# Giao_Thong.net
KiCad netlist of a schematic drawn in Altium Designer
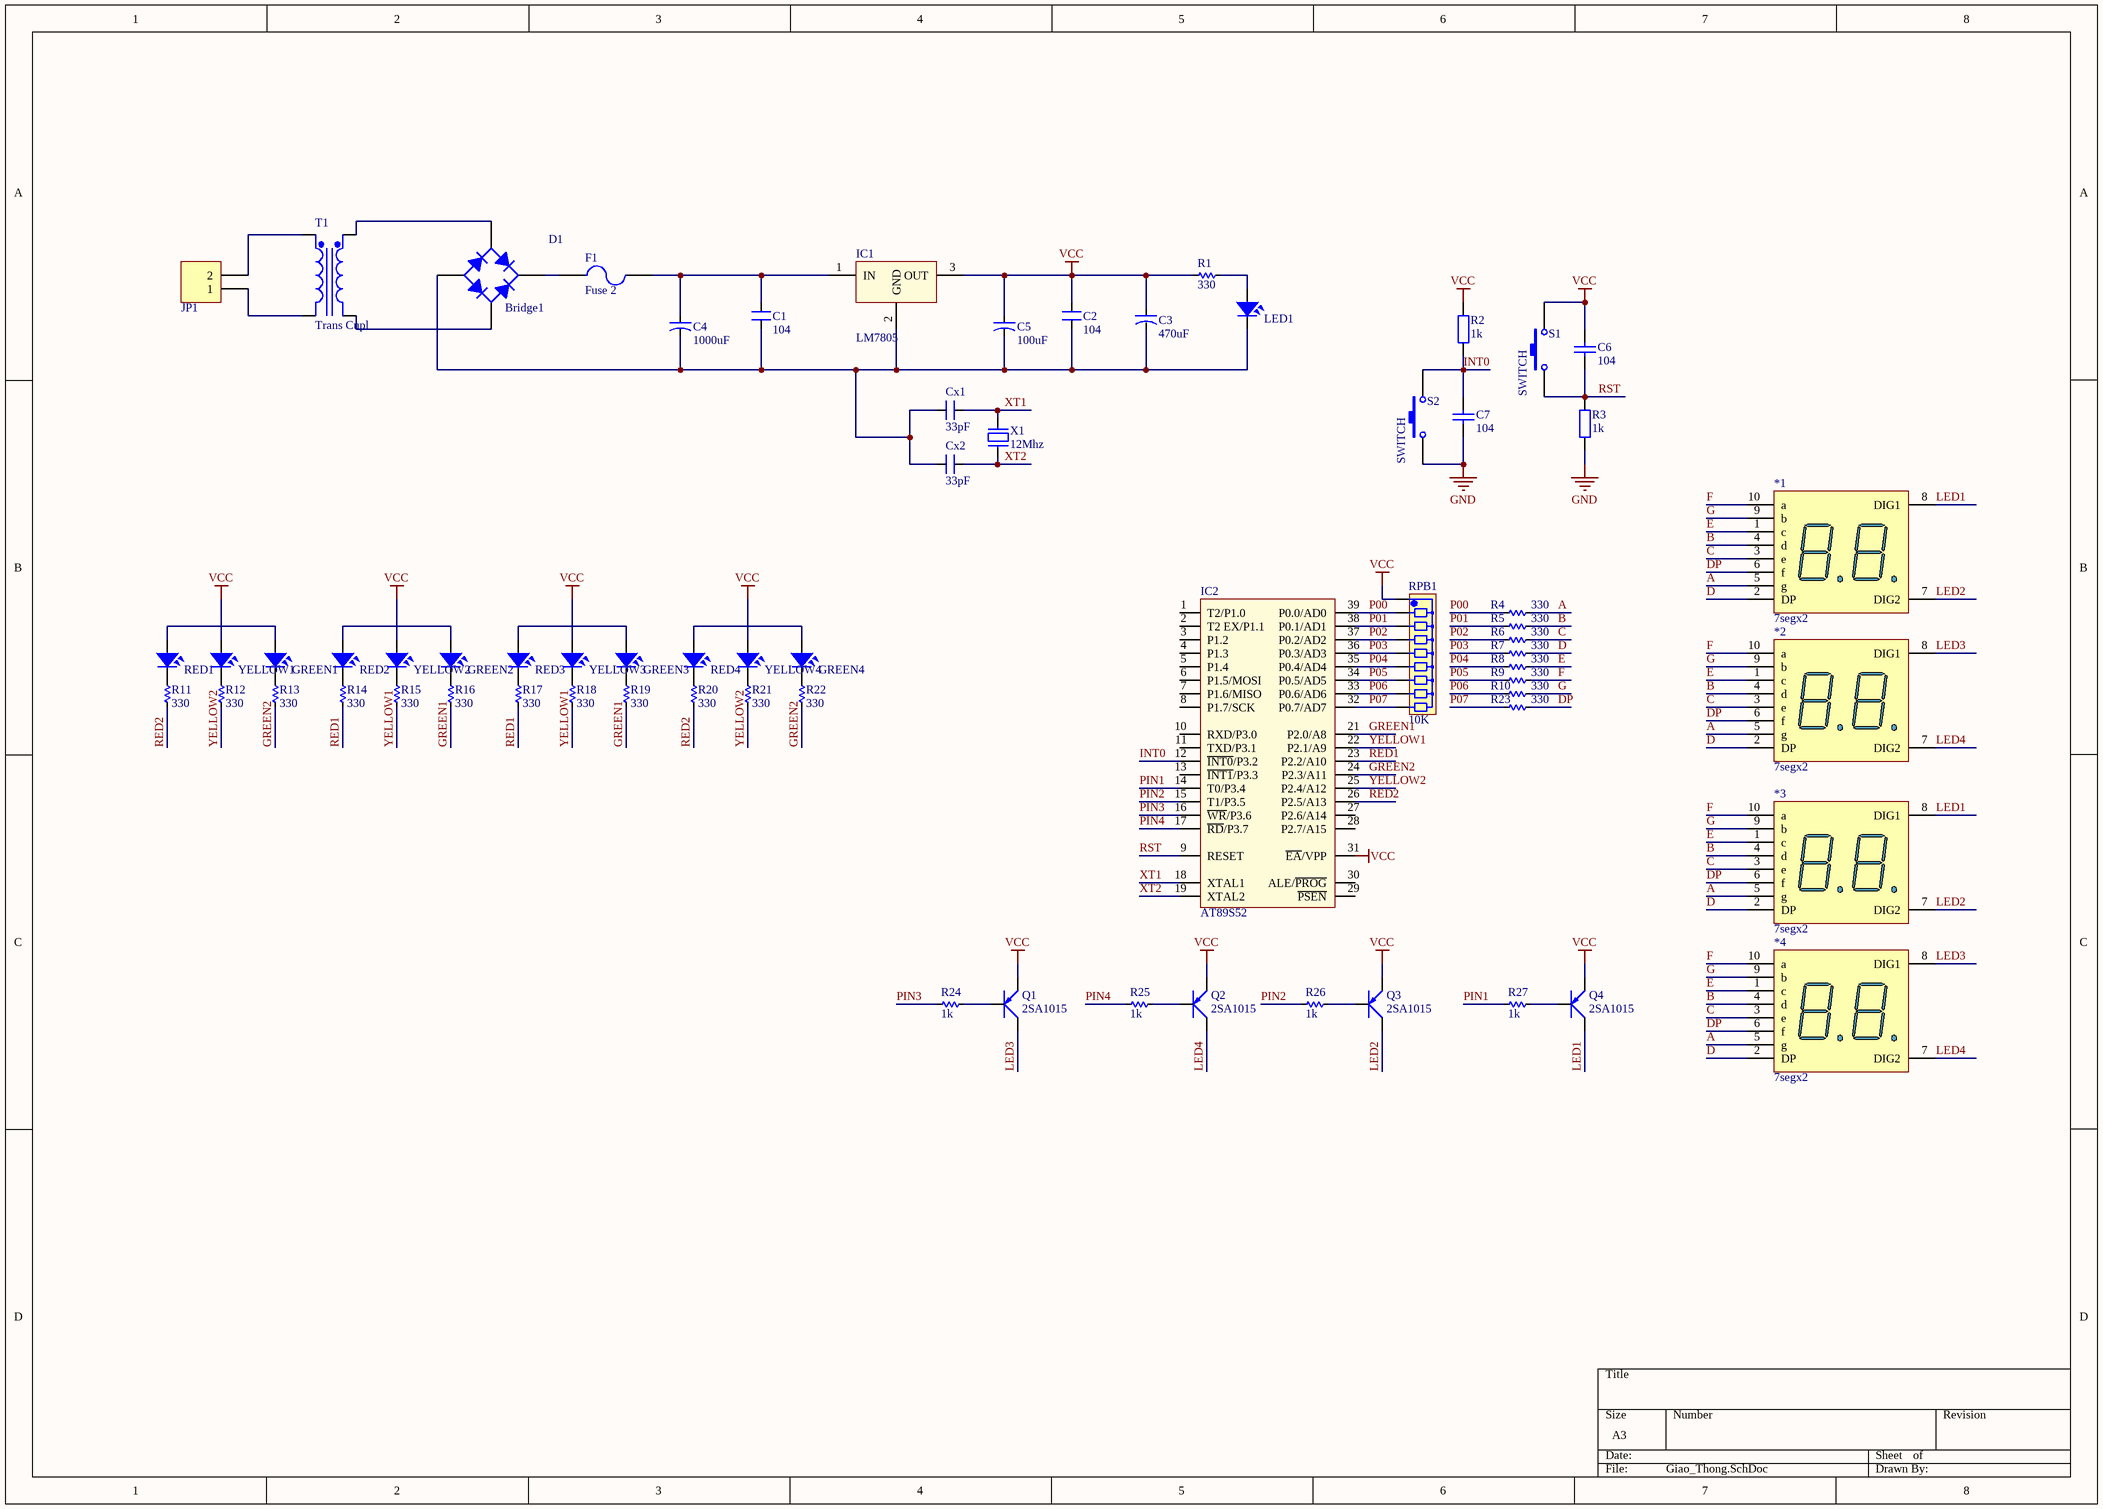
[diagram p0: Giao_Thong.SchDoc]

(export (version "E")
  (design (tool "Eeschema 10.0.6"))
  (components
    (comp (ref "*1") (value "7segx2") (footprint "7segx2") (libsource (lib "led7segx2_A") (part "7segx2")))
    (comp (ref "*2") (value "7segx2") (footprint "7segx2") (libsource (lib "led7segx2_A") (part "7segx2")))
    (comp (ref "*3") (value "7segx2") (footprint "7segx2") (libsource (lib "led7segx2_A") (part "7segx2")))
    (comp (ref "*4") (value "7segx2") (footprint "7segx2") (libsource (lib "led7segx2_A") (part "7segx2")))
    (comp (ref "C1")
      (value "104")
      (footprint "CN2")
      (description "Cap np 104 => 105pF")
      (libsource (lib "thietke") (part "CN2"))
    )
    (comp (ref "C2")
      (value "104")
      (footprint "CN2")
      (description "Cap np 104 => 105pF")
      (libsource (lib "thietke") (part "CN2"))
    )
    (comp (ref "C3")
      (value "470uF")
      (footprint "CA-ALU-8")
      (description "Capacitor (Semiconductor SIM Model)")
      (fields (field (name "PUBLISHER") "Altium Limited"))
      (libsource (lib "Giao_Thong") (part "CN-ALU-DIP"))
    )
    (comp (ref "C4")
      (value "1000uF")
      (footprint "CA-ALU-8")
      (description "Capacitor (Semiconductor SIM Model)")
      (fields (field (name "PUBLISHER") "Altium Limited"))
      (libsource (lib "Giao_Thong") (part "CN-ALU-DIP"))
    )
    (comp (ref "C5")
      (value "100uF")
      (footprint "CA-ALU-8")
      (description "Capacitor (Semiconductor SIM Model)")
      (fields (field (name "PUBLISHER") "Altium Limited"))
      (libsource (lib "Giao_Thong") (part "CN-ALU-DIP"))
    )
    (comp (ref "C6")
      (value "104")
      (footprint "0805 CAP")
      (fields (field (name "PUBLISHER") "Altium Limited"))
      (libsource (lib "ThinhNguyenLib") (part "CAP CERAMIC"))
    )
    (comp (ref "C7")
      (value "104")
      (footprint "0805 CAP")
      (fields (field (name "PUBLISHER") "Altium Limited"))
      (libsource (lib "ThinhNguyenLib") (part "CAP CERAMIC"))
    )
    (comp (ref "Cx1") (value "33pF") (footprint "CN1") (libsource (lib "LIBRARY") (part "CN")))
    (comp (ref "Cx2") (value "33pF") (footprint "CN1") (libsource (lib "LIBRARY") (part "CN")))
    (comp (ref "D1")
      (value "Bridge1")
      (footprint "E-BIP-P4/D10")
      (description "Full Wave Diode Bridge")
      (fields (field (name "PUBLISHER") "Altium Limited"))
      (libsource (lib "Miscellaneous Devices") (part "Bridge1"))
    )
    (comp (ref "F1")
      (value "Fuse 2")
      (footprint "PIN-W2/E2.8")
      (description "Fuse")
      (fields (field (name "PUBLISHER") "Altium Limited"))
      (libsource (lib "Miscellaneous Devices") (part "Fuse 2"))
    )
    (comp (ref "GREEN1")
      (value "LED")
      (footprint "LED-5-Green")
      (description "LED Single colour Green and Red")
      (libsource (lib "LIBRARY") (part "LED"))
    )
    (comp (ref "GREEN2")
      (value "LED")
      (footprint "LED-5-Green")
      (description "LED Single colour Green and Red")
      (libsource (lib "LIBRARY") (part "LED"))
    )
    (comp (ref "GREEN3")
      (value "LED")
      (footprint "LED-5-Green")
      (description "LED Single colour Green and Red")
      (libsource (lib "LIBRARY") (part "LED"))
    )
    (comp (ref "GREEN4")
      (value "LED")
      (footprint "LED-5-Green")
      (description "LED Single colour Green and Red")
      (libsource (lib "LIBRARY") (part "LED"))
    )
    (comp (ref "IC1")
      (value "LM7805")
      (footprint "QTO-220")
      (description "On ap +, from + 5 to + 24VDC")
      (libsource (lib "thietke") (part "LM78xx"))
    )
    (comp (ref "IC2")
      (value "AT89S52")
      (footprint "DIP40/W0.6")
      (description "AT89S52, 8k Byte Flash Memory , 40 Pin")
      (libsource (lib "LIBRARY") (part "AT89S52"))
    )
    (comp (ref "JP1")
      (value "Header 2_1")
      (footprint "HED2")
      (description "Header, 2-Pin")
      (fields (field (name "MANUFACTURER") "Generic Components"))
      (libsource (lib "thietke") (part "Header 2_1"))
    )
    (comp (ref "LED1")
      (value "LED")
      (footprint "LED-5MM-RED")
      (description "LED Single colour Green and Red")
      (libsource (lib "LIBRARY") (part "LED"))
    )
    (comp (ref "Q1")
      (value "2SA1015")
      (footprint "TO92-123")
      (description "PNP 600mW, ECB")
      (libsource (lib "LIBRARY") (part "2SA1015"))
    )
    (comp (ref "Q2")
      (value "2SA1015")
      (footprint "TO92-123")
      (description "PNP 600mW, ECB")
      (libsource (lib "LIBRARY") (part "2SA1015"))
    )
    (comp (ref "Q3")
      (value "2SA1015")
      (footprint "TO92-123")
      (description "PNP 600mW, ECB")
      (libsource (lib "LIBRARY") (part "2SA1015"))
    )
    (comp (ref "Q4")
      (value "2SA1015")
      (footprint "TO92-123")
      (description "PNP 600mW, ECB")
      (libsource (lib "LIBRARY") (part "2SA1015"))
    )
    (comp (ref "R1")
      (value "330")
      (footprint "RES-1/4W")
      (description "Res")
      (fields
        (field (name "MANUFACTURER") "Generic Components")
        (field (name "PUBLISHER") "Altium Hobart Technology Centre")
      )
      (libsource (lib "LIBRARY") (part "Res"))
    )
    (comp (ref "R2")
      (value "1k")
      (footprint "0805 RESISTOR")
      (libsource (lib "ThinhNguyenLib") (part "RESISTOR"))
    )
    (comp (ref "R3")
      (value "1k")
      (footprint "0805 RESISTOR")
      (libsource (lib "ThinhNguyenLib") (part "RESISTOR"))
    )
    (comp (ref "R4")
      (value "330")
      (footprint "RES-SMD-0805")
      (description "Resistor")
      (fields
        (field (name "MANUFACTURER") "Generic Components")
        (field (name "PUBLISHER") "Altium Hobart Technology Centre")
      )
      (libsource (lib "LIBRARY") (part "Res-SMD"))
    )
    (comp (ref "R5")
      (value "330")
      (footprint "RES-SMD-0805")
      (description "Resistor")
      (fields
        (field (name "MANUFACTURER") "Generic Components")
        (field (name "PUBLISHER") "Altium Hobart Technology Centre")
      )
      (libsource (lib "LIBRARY") (part "Res-SMD"))
    )
    (comp (ref "R6")
      (value "330")
      (footprint "RES-SMD-0805")
      (description "Resistor")
      (fields
        (field (name "MANUFACTURER") "Generic Components")
        (field (name "PUBLISHER") "Altium Hobart Technology Centre")
      )
      (libsource (lib "LIBRARY") (part "Res-SMD"))
    )
    (comp (ref "R7")
      (value "330")
      (footprint "RES-SMD-0805")
      (description "Resistor")
      (fields
        (field (name "MANUFACTURER") "Generic Components")
        (field (name "PUBLISHER") "Altium Hobart Technology Centre")
      )
      (libsource (lib "LIBRARY") (part "Res-SMD"))
    )
    (comp (ref "R8")
      (value "330")
      (footprint "RES-SMD-0805")
      (description "Resistor")
      (fields
        (field (name "MANUFACTURER") "Generic Components")
        (field (name "PUBLISHER") "Altium Hobart Technology Centre")
      )
      (libsource (lib "LIBRARY") (part "Res-SMD"))
    )
    (comp (ref "R9")
      (value "330")
      (footprint "RES-SMD-0805")
      (description "Resistor")
      (fields
        (field (name "MANUFACTURER") "Generic Components")
        (field (name "PUBLISHER") "Altium Hobart Technology Centre")
      )
      (libsource (lib "LIBRARY") (part "Res-SMD"))
    )
    (comp (ref "R10")
      (value "330")
      (footprint "RES-SMD-0805")
      (description "Resistor")
      (fields
        (field (name "MANUFACTURER") "Generic Components")
        (field (name "PUBLISHER") "Altium Hobart Technology Centre")
      )
      (libsource (lib "LIBRARY") (part "Res-SMD"))
    )
    (comp (ref "R11")
      (value "330")
      (footprint "RES-SMD-0805")
      (description "Resistor")
      (fields
        (field (name "MANUFACTURER") "Generic Components")
        (field (name "PUBLISHER") "Altium Hobart Technology Centre")
      )
      (libsource (lib "LIBRARY") (part "Res-SMD"))
    )
    (comp (ref "R12")
      (value "330")
      (footprint "RES-SMD-0805")
      (description "Resistor")
      (fields
        (field (name "MANUFACTURER") "Generic Components")
        (field (name "PUBLISHER") "Altium Hobart Technology Centre")
      )
      (libsource (lib "LIBRARY") (part "Res-SMD"))
    )
    (comp (ref "R13")
      (value "330")
      (footprint "RES-SMD-0805")
      (description "Resistor")
      (fields
        (field (name "MANUFACTURER") "Generic Components")
        (field (name "PUBLISHER") "Altium Hobart Technology Centre")
      )
      (libsource (lib "LIBRARY") (part "Res-SMD"))
    )
    (comp (ref "R14")
      (value "330")
      (footprint "RES-SMD-0805")
      (description "Resistor")
      (fields
        (field (name "MANUFACTURER") "Generic Components")
        (field (name "PUBLISHER") "Altium Hobart Technology Centre")
      )
      (libsource (lib "LIBRARY") (part "Res-SMD"))
    )
    (comp (ref "R15")
      (value "330")
      (footprint "RES-SMD-0805")
      (description "Resistor")
      (fields
        (field (name "MANUFACTURER") "Generic Components")
        (field (name "PUBLISHER") "Altium Hobart Technology Centre")
      )
      (libsource (lib "LIBRARY") (part "Res-SMD"))
    )
    (comp (ref "R16")
      (value "330")
      (footprint "RES-SMD-0805")
      (description "Resistor")
      (fields
        (field (name "MANUFACTURER") "Generic Components")
        (field (name "PUBLISHER") "Altium Hobart Technology Centre")
      )
      (libsource (lib "LIBRARY") (part "Res-SMD"))
    )
    (comp (ref "R17")
      (value "330")
      (footprint "RES-SMD-0805")
      (description "Resistor")
      (fields
        (field (name "MANUFACTURER") "Generic Components")
        (field (name "PUBLISHER") "Altium Hobart Technology Centre")
      )
      (libsource (lib "LIBRARY") (part "Res-SMD"))
    )
    (comp (ref "R18")
      (value "330")
      (footprint "RES-SMD-0805")
      (description "Resistor")
      (fields
        (field (name "MANUFACTURER") "Generic Components")
        (field (name "PUBLISHER") "Altium Hobart Technology Centre")
      )
      (libsource (lib "LIBRARY") (part "Res-SMD"))
    )
    (comp (ref "R19")
      (value "330")
      (footprint "RES-SMD-0805")
      (description "Resistor")
      (fields
        (field (name "MANUFACTURER") "Generic Components")
        (field (name "PUBLISHER") "Altium Hobart Technology Centre")
      )
      (libsource (lib "LIBRARY") (part "Res-SMD"))
    )
    (comp (ref "R20")
      (value "330")
      (footprint "RES-SMD-0805")
      (description "Resistor")
      (fields
        (field (name "MANUFACTURER") "Generic Components")
        (field (name "PUBLISHER") "Altium Hobart Technology Centre")
      )
      (libsource (lib "LIBRARY") (part "Res-SMD"))
    )
    (comp (ref "R21")
      (value "330")
      (footprint "RES-SMD-0805")
      (description "Resistor")
      (fields
        (field (name "MANUFACTURER") "Generic Components")
        (field (name "PUBLISHER") "Altium Hobart Technology Centre")
      )
      (libsource (lib "LIBRARY") (part "Res-SMD"))
    )
    (comp (ref "R22")
      (value "330")
      (footprint "RES-SMD-0805")
      (description "Resistor")
      (fields
        (field (name "MANUFACTURER") "Generic Components")
        (field (name "PUBLISHER") "Altium Hobart Technology Centre")
      )
      (libsource (lib "LIBRARY") (part "Res-SMD"))
    )
    (comp (ref "R23")
      (value "330")
      (footprint "RES-SMD-0805")
      (description "Resistor")
      (fields
        (field (name "MANUFACTURER") "Generic Components")
        (field (name "PUBLISHER") "Altium Hobart Technology Centre")
      )
      (libsource (lib "LIBRARY") (part "Res-SMD"))
    )
    (comp (ref "R24")
      (value "1k")
      (footprint "RES-SMD-0805")
      (description "Resistor")
      (fields
        (field (name "MANUFACTURER") "Generic Components")
        (field (name "PUBLISHER") "Altium Hobart Technology Centre")
      )
      (libsource (lib "LIBRARY") (part "Res-SMD"))
    )
    (comp (ref "R25")
      (value "1k")
      (footprint "RES-SMD-0805")
      (description "Resistor")
      (fields
        (field (name "MANUFACTURER") "Generic Components")
        (field (name "PUBLISHER") "Altium Hobart Technology Centre")
      )
      (libsource (lib "LIBRARY") (part "Res-SMD"))
    )
    (comp (ref "R26")
      (value "1k")
      (footprint "RES-SMD-0805")
      (description "Resistor")
      (fields
        (field (name "MANUFACTURER") "Generic Components")
        (field (name "PUBLISHER") "Altium Hobart Technology Centre")
      )
      (libsource (lib "LIBRARY") (part "Res-SMD"))
    )
    (comp (ref "R27")
      (value "1k")
      (footprint "RES-SMD-0805")
      (description "Resistor")
      (fields
        (field (name "MANUFACTURER") "Generic Components")
        (field (name "PUBLISHER") "Altium Hobart Technology Centre")
      )
      (libsource (lib "LIBRARY") (part "Res-SMD"))
    )
    (comp (ref "RED1")
      (value "LED")
      (footprint "LED-5-RED")
      (description "LED Single colour Green and Red")
      (libsource (lib "LIBRARY") (part "LED"))
    )
    (comp (ref "RED2")
      (value "LED")
      (footprint "LED-5-RED")
      (description "LED Single colour Green and Red")
      (libsource (lib "LIBRARY") (part "LED"))
    )
    (comp (ref "RED3")
      (value "LED")
      (footprint "LED-5-RED")
      (description "LED Single colour Green and Red")
      (libsource (lib "LIBRARY") (part "LED"))
    )
    (comp (ref "RED4")
      (value "LED")
      (footprint "LED-5-RED")
      (description "LED Single colour Green and Red")
      (libsource (lib "LIBRARY") (part "LED"))
    )
    (comp (ref "RPB1")
      (value "10K")
      (footprint "RN8")
      (description "Resistor 8 (Thanh)")
      (libsource (lib "LIBRARY") (part "RN8"))
    )
    (comp (ref "S1")
      (value "SWITCH")
      (footprint "SW 4PIN")
      (fields (field (name "PUBLISHER") "Altium Limited"))
      (libsource (lib "ThinhNguyenLib") (part "SWITCH"))
    )
    (comp (ref "S2")
      (value "SWITCH")
      (footprint "SW 4PIN")
      (fields (field (name "PUBLISHER") "Altium Limited"))
      (libsource (lib "ThinhNguyenLib") (part "SWITCH"))
    )
    (comp (ref "T1")
      (value "Trans Cupl")
      (footprint "TRF_4")
      (description "Transformer (Coupled Inductor Model)")
      (fields (field (name "PUBLISHER") "Altium Limited"))
      (libsource (lib "Miscellaneous Devices") (part "Trans Cupl"))
    )
    (comp (ref "X1")
      (value "12Mhz")
      (footprint "XT2")
      (description "Crystal, 32.768 KHz, -40 to 85 degC, 3.2 x 1.5 x 0.9 mm SMD")
      (libsource (lib "LIBRARY") (part "XT2"))
    )
    (comp (ref "YELLOW1")
      (value "LED")
      (footprint "LED-5-Yellow")
      (description "LED Single colour Green and Red")
      (libsource (lib "LIBRARY") (part "LED"))
    )
    (comp (ref "YELLOW2")
      (value "LED")
      (footprint "LED-5-Yellow")
      (description "LED Single colour Green and Red")
      (libsource (lib "LIBRARY") (part "LED"))
    )
    (comp (ref "YELLOW3")
      (value "LED")
      (footprint "LED-5-Yellow")
      (description "LED Single colour Green and Red")
      (libsource (lib "LIBRARY") (part "LED"))
    )
    (comp (ref "YELLOW4")
      (value "LED")
      (footprint "LED-5-Yellow")
      (description "LED Single colour Green and Red")
      (libsource (lib "LIBRARY") (part "LED"))
    )
  )
  (nets
    (net (code "1") (name "/A") (class "Default")
      (node (ref "*1") (pin "5") (pinfunction "g_5") (pintype "passive"))
      (node (ref "*2") (pin "5") (pinfunction "g_5") (pintype "passive"))
      (node (ref "*3") (pin "5") (pinfunction "g_5") (pintype "passive"))
      (node (ref "*4") (pin "5") (pinfunction "g_5") (pintype "passive"))
      (node (ref "R4") (pin "1") (pinfunction "1_1") (pintype "passive"))
    )
    (net (code "2") (name "/B") (class "Default")
      (node (ref "*1") (pin "4") (pinfunction "d_4") (pintype "passive"))
      (node (ref "*2") (pin "4") (pinfunction "d_4") (pintype "passive"))
      (node (ref "*3") (pin "4") (pinfunction "d_4") (pintype "passive"))
      (node (ref "*4") (pin "4") (pinfunction "d_4") (pintype "passive"))
      (node (ref "R5") (pin "1") (pinfunction "1_1") (pintype "passive"))
    )
    (net (code "3") (name "/C") (class "Default")
      (node (ref "*1") (pin "3") (pinfunction "e_3") (pintype "passive"))
      (node (ref "*2") (pin "3") (pinfunction "e_3") (pintype "passive"))
      (node (ref "*3") (pin "3") (pinfunction "e_3") (pintype "passive"))
      (node (ref "*4") (pin "3") (pinfunction "e_3") (pintype "passive"))
      (node (ref "R6") (pin "1") (pinfunction "1_1") (pintype "passive"))
    )
    (net (code "4") (name "/D") (class "Default")
      (node (ref "*1") (pin "2") (pinfunction "DP_2") (pintype "passive"))
      (node (ref "*2") (pin "2") (pinfunction "DP_2") (pintype "passive"))
      (node (ref "*3") (pin "2") (pinfunction "DP_2") (pintype "passive"))
      (node (ref "*4") (pin "2") (pinfunction "DP_2") (pintype "passive"))
      (node (ref "R7") (pin "1") (pinfunction "1_1") (pintype "passive"))
    )
    (net (code "5") (name "/DP") (class "Default")
      (node (ref "*1") (pin "6") (pinfunction "f_6") (pintype "passive"))
      (node (ref "*2") (pin "6") (pinfunction "f_6") (pintype "passive"))
      (node (ref "*3") (pin "6") (pinfunction "f_6") (pintype "passive"))
      (node (ref "*4") (pin "6") (pinfunction "f_6") (pintype "passive"))
      (node (ref "R23") (pin "1") (pinfunction "1_1") (pintype "passive"))
    )
    (net (code "6") (name "/E") (class "Default")
      (node (ref "*1") (pin "1") (pinfunction "c_1") (pintype "passive"))
      (node (ref "*2") (pin "1") (pinfunction "c_1") (pintype "passive"))
      (node (ref "*3") (pin "1") (pinfunction "c_1") (pintype "passive"))
      (node (ref "*4") (pin "1") (pinfunction "c_1") (pintype "passive"))
      (node (ref "R8") (pin "1") (pinfunction "1_1") (pintype "passive"))
    )
    (net (code "7") (name "/F") (class "Default")
      (node (ref "*1") (pin "10") (pinfunction "a_10") (pintype "passive"))
      (node (ref "*2") (pin "10") (pinfunction "a_10") (pintype "passive"))
      (node (ref "*3") (pin "10") (pinfunction "a_10") (pintype "passive"))
      (node (ref "*4") (pin "10") (pinfunction "a_10") (pintype "passive"))
      (node (ref "R9") (pin "1") (pinfunction "1_1") (pintype "passive"))
    )
    (net (code "8") (name "/G") (class "Default")
      (node (ref "*1") (pin "9") (pinfunction "b_9") (pintype "passive"))
      (node (ref "*2") (pin "9") (pinfunction "b_9") (pintype "passive"))
      (node (ref "*3") (pin "9") (pinfunction "b_9") (pintype "passive"))
      (node (ref "*4") (pin "9") (pinfunction "b_9") (pintype "passive"))
      (node (ref "R10") (pin "1") (pinfunction "1_1") (pintype "passive"))
    )
    (net (code "9") (name "/GREEN1") (class "Default")
      (node (ref "IC2") (pin "21") (pinfunction "P2.0/A8_21") (pintype "passive"))
      (node (ref "R16") (pin "1") (pinfunction "1_1") (pintype "passive"))
      (node (ref "R19") (pin "1") (pinfunction "1_1") (pintype "passive"))
    )
    (net (code "10") (name "/GREEN2") (class "Default")
      (node (ref "IC2") (pin "24") (pinfunction "P2.3/A11_24") (pintype "passive"))
      (node (ref "R13") (pin "1") (pinfunction "1_1") (pintype "passive"))
      (node (ref "R22") (pin "1") (pinfunction "1_1") (pintype "passive"))
    )
    (net (code "11") (name "/INT0") (class "Default")
      (node (ref "C7") (pin "2") (pinfunction "2_2") (pintype "passive"))
      (node (ref "IC2") (pin "12") (pinfunction "~{INT0}/P3.2_12") (pintype "passive"))
      (node (ref "R2") (pin "2") (pinfunction "2_2") (pintype "passive"))
      (node (ref "S2") (pin "2") (pinfunction "2_2") (pintype "passive"))
    )
    (net (code "12") (name "/LED1") (class "Default")
      (node (ref "*1") (pin "8") (pinfunction "DIG1_8") (pintype "passive"))
      (node (ref "*3") (pin "8") (pinfunction "DIG1_8") (pintype "passive"))
      (node (ref "Q4") (pin "2") (pinfunction "C_2") (pintype "passive"))
    )
    (net (code "13") (name "/LED2") (class "Default")
      (node (ref "*1") (pin "7") (pinfunction "DIG2_7") (pintype "passive"))
      (node (ref "*3") (pin "7") (pinfunction "DIG2_7") (pintype "passive"))
      (node (ref "Q3") (pin "2") (pinfunction "C_2") (pintype "passive"))
    )
    (net (code "14") (name "/LED3") (class "Default")
      (node (ref "*2") (pin "8") (pinfunction "DIG1_8") (pintype "passive"))
      (node (ref "*4") (pin "8") (pinfunction "DIG1_8") (pintype "passive"))
      (node (ref "Q1") (pin "2") (pinfunction "C_2") (pintype "passive"))
    )
    (net (code "15") (name "/LED4") (class "Default")
      (node (ref "*2") (pin "7") (pinfunction "DIG2_7") (pintype "passive"))
      (node (ref "*4") (pin "7") (pinfunction "DIG2_7") (pintype "passive"))
      (node (ref "Q2") (pin "2") (pinfunction "C_2") (pintype "passive"))
    )
    (net (code "16") (name "/P00") (class "Default")
      (node (ref "IC2") (pin "39") (pinfunction "P0.0/AD0_39") (pintype "passive"))
      (node (ref "R4") (pin "2") (pinfunction "2_2") (pintype "passive"))
      (node (ref "RPB1") (pin "2") (pinfunction "2_2") (pintype "passive"))
    )
    (net (code "17") (name "/P01") (class "Default")
      (node (ref "IC2") (pin "38") (pinfunction "P0.1/AD1_38") (pintype "passive"))
      (node (ref "R5") (pin "2") (pinfunction "2_2") (pintype "passive"))
      (node (ref "RPB1") (pin "3") (pinfunction "3_3") (pintype "passive"))
    )
    (net (code "18") (name "/P02") (class "Default")
      (node (ref "IC2") (pin "37") (pinfunction "P0.2/AD2_37") (pintype "passive"))
      (node (ref "R6") (pin "2") (pinfunction "2_2") (pintype "passive"))
      (node (ref "RPB1") (pin "4") (pinfunction "4_4") (pintype "passive"))
    )
    (net (code "19") (name "/P03") (class "Default")
      (node (ref "IC2") (pin "36") (pinfunction "P0.3/AD3_36") (pintype "passive"))
      (node (ref "R7") (pin "2") (pinfunction "2_2") (pintype "passive"))
      (node (ref "RPB1") (pin "5") (pinfunction "5_5") (pintype "passive"))
    )
    (net (code "20") (name "/P04") (class "Default")
      (node (ref "IC2") (pin "35") (pinfunction "P0.4/AD4_35") (pintype "passive"))
      (node (ref "R8") (pin "2") (pinfunction "2_2") (pintype "passive"))
      (node (ref "RPB1") (pin "6") (pinfunction "6_6") (pintype "passive"))
    )
    (net (code "21") (name "/P05") (class "Default")
      (node (ref "IC2") (pin "34") (pinfunction "P0.5/AD5_34") (pintype "passive"))
      (node (ref "R9") (pin "2") (pinfunction "2_2") (pintype "passive"))
      (node (ref "RPB1") (pin "7") (pinfunction "7_7") (pintype "passive"))
    )
    (net (code "22") (name "/P06") (class "Default")
      (node (ref "IC2") (pin "33") (pinfunction "P0.6/AD6_33") (pintype "passive"))
      (node (ref "R10") (pin "2") (pinfunction "2_2") (pintype "passive"))
      (node (ref "RPB1") (pin "8") (pinfunction "8_8") (pintype "passive"))
    )
    (net (code "23") (name "/P07") (class "Default")
      (node (ref "IC2") (pin "32") (pinfunction "P0.7/AD7_32") (pintype "passive"))
      (node (ref "R23") (pin "2") (pinfunction "2_2") (pintype "passive"))
      (node (ref "RPB1") (pin "9") (pinfunction "9_9") (pintype "passive"))
    )
    (net (code "24") (name "/PIN1") (class "Default")
      (node (ref "IC2") (pin "14") (pinfunction "T0/P3.4_14") (pintype "passive"))
      (node (ref "R27") (pin "2") (pinfunction "2_2") (pintype "passive"))
    )
    (net (code "25") (name "/PIN2") (class "Default")
      (node (ref "IC2") (pin "15") (pinfunction "T1/P3.5_15") (pintype "passive"))
      (node (ref "R26") (pin "2") (pinfunction "2_2") (pintype "passive"))
    )
    (net (code "26") (name "/PIN3") (class "Default")
      (node (ref "IC2") (pin "16") (pinfunction "~{WR}/P3.6_16") (pintype "passive"))
      (node (ref "R24") (pin "2") (pinfunction "2_2") (pintype "passive"))
    )
    (net (code "27") (name "/PIN4") (class "Default")
      (node (ref "IC2") (pin "17") (pinfunction "~{RD}/P3.7_17") (pintype "passive"))
      (node (ref "R25") (pin "2") (pinfunction "2_2") (pintype "passive"))
    )
    (net (code "28") (name "/RED1") (class "Default")
      (node (ref "IC2") (pin "23") (pinfunction "P2.2/A10_23") (pintype "passive"))
      (node (ref "R14") (pin "1") (pinfunction "1_1") (pintype "passive"))
      (node (ref "R17") (pin "1") (pinfunction "1_1") (pintype "passive"))
    )
    (net (code "29") (name "/RED2") (class "Default")
      (node (ref "IC2") (pin "26") (pinfunction "P2.5/A13_26") (pintype "passive"))
      (node (ref "R11") (pin "1") (pinfunction "1_1") (pintype "passive"))
      (node (ref "R20") (pin "1") (pinfunction "1_1") (pintype "passive"))
    )
    (net (code "30") (name "/RST") (class "Default")
      (node (ref "C6") (pin "1") (pinfunction "1_1") (pintype "passive"))
      (node (ref "IC2") (pin "9") (pinfunction "RESET_9") (pintype "passive"))
      (node (ref "R3") (pin "1") (pinfunction "1_1") (pintype "passive"))
      (node (ref "S1") (pin "1") (pinfunction "1_1") (pintype "passive"))
    )
    (net (code "31") (name "/XT1") (class "Default")
      (node (ref "Cx1") (pin "2") (pinfunction "2_2") (pintype "passive"))
      (node (ref "IC2") (pin "18") (pinfunction "XTAL1_18") (pintype "passive"))
      (node (ref "X1") (pin "2") (pinfunction "2_2") (pintype "passive"))
    )
    (net (code "32") (name "/XT2") (class "Default")
      (node (ref "Cx2") (pin "2") (pinfunction "2_2") (pintype "passive"))
      (node (ref "IC2") (pin "19") (pinfunction "XTAL2_19") (pintype "passive"))
      (node (ref "X1") (pin "1") (pinfunction "1_1") (pintype "passive"))
    )
    (net (code "33") (name "/YELLOW1") (class "Default")
      (node (ref "IC2") (pin "22") (pinfunction "P2.1/A9_22") (pintype "passive"))
      (node (ref "R15") (pin "1") (pinfunction "1_1") (pintype "passive"))
      (node (ref "R18") (pin "1") (pinfunction "1_1") (pintype "passive"))
    )
    (net (code "34") (name "/YELLOW2") (class "Default")
      (node (ref "IC2") (pin "25") (pinfunction "P2.4/A12_25") (pintype "passive"))
      (node (ref "R12") (pin "1") (pinfunction "1_1") (pintype "passive"))
      (node (ref "R21") (pin "1") (pinfunction "1_1") (pintype "passive"))
    )
    (net (code "35") (name "GND") (class "Default")
      (node (ref "C7") (pin "1") (pinfunction "1_1") (pintype "passive"))
      (node (ref "IC2") (pin "20") (pinfunction "GND_20") (pintype "power_in"))
      (node (ref "R3") (pin "2") (pinfunction "2_2") (pintype "passive"))
      (node (ref "S2") (pin "1") (pinfunction "1_1") (pintype "passive"))
    )
    (net (code "36") (name "Net-(D1-A)") (class "Default")
      (node (ref "C1") (pin "1") (pinfunction "1_1") (pintype "passive"))
      (node (ref "C2") (pin "1") (pinfunction "1_1") (pintype "passive"))
      (node (ref "C3") (pin "2") (pinfunction "2_2") (pintype "passive"))
      (node (ref "C4") (pin "2") (pinfunction "2_2") (pintype "passive"))
      (node (ref "C5") (pin "2") (pinfunction "2_2") (pintype "passive"))
      (node (ref "Cx1") (pin "1") (pinfunction "1_1") (pintype "passive"))
      (node (ref "Cx2") (pin "1") (pinfunction "1_1") (pintype "passive"))
      (node (ref "D1") (pin "3") (pinfunction "A_3") (pintype "passive"))
      (node (ref "IC1") (pin "2") (pinfunction "GND_2") (pintype "passive"))
      (node (ref "LED1") (pin "2") (pinfunction "2_2") (pintype "passive"))
    )
    (net (code "37") (name "Net-(D1-K)") (class "Default")
      (node (ref "D1") (pin "1") (pinfunction "K_1") (pintype "passive"))
      (node (ref "F1") (pin "1") (pinfunction "1_1") (pintype "passive"))
    )
    (net (code "38") (name "Net-(GREEN1-Pad1)") (class "Default")
      (node (ref "GREEN1") (pin "1") (pinfunction "1_1") (pintype "passive"))
      (node (ref "RED1") (pin "1") (pinfunction "1_1") (pintype "passive"))
    )
    (net (code "39") (name "Net-(GREEN1-Pad2)") (class "Default")
      (node (ref "GREEN1") (pin "2") (pinfunction "2_2") (pintype "passive"))
      (node (ref "R13") (pin "2") (pinfunction "2_2") (pintype "passive"))
    )
    (net (code "40") (name "Net-(GREEN2-Pad1)") (class "Default")
      (node (ref "GREEN2") (pin "1") (pinfunction "1_1") (pintype "passive"))
      (node (ref "RED2") (pin "1") (pinfunction "1_1") (pintype "passive"))
    )
    (net (code "41") (name "Net-(GREEN2-Pad2)") (class "Default")
      (node (ref "GREEN2") (pin "2") (pinfunction "2_2") (pintype "passive"))
      (node (ref "R16") (pin "2") (pinfunction "2_2") (pintype "passive"))
    )
    (net (code "42") (name "Net-(GREEN3-Pad1)") (class "Default")
      (node (ref "GREEN3") (pin "1") (pinfunction "1_1") (pintype "passive"))
      (node (ref "RED3") (pin "1") (pinfunction "1_1") (pintype "passive"))
    )
    (net (code "43") (name "Net-(GREEN3-Pad2)") (class "Default")
      (node (ref "GREEN3") (pin "2") (pinfunction "2_2") (pintype "passive"))
      (node (ref "R19") (pin "2") (pinfunction "2_2") (pintype "passive"))
    )
    (net (code "44") (name "Net-(GREEN4-Pad1)") (class "Default")
      (node (ref "GREEN4") (pin "1") (pinfunction "1_1") (pintype "passive"))
      (node (ref "RED4") (pin "1") (pinfunction "1_1") (pintype "passive"))
    )
    (net (code "45") (name "Net-(GREEN4-Pad2)") (class "Default")
      (node (ref "GREEN4") (pin "2") (pinfunction "2_2") (pintype "passive"))
      (node (ref "R22") (pin "2") (pinfunction "2_2") (pintype "passive"))
    )
    (net (code "46") (name "Net-(IC1-IN)") (class "Default")
      (node (ref "C1") (pin "2") (pinfunction "2_2") (pintype "passive"))
      (node (ref "C4") (pin "1") (pinfunction "1_1") (pintype "passive"))
      (node (ref "F1") (pin "2") (pinfunction "2_2") (pintype "passive"))
      (node (ref "IC1") (pin "1") (pinfunction "IN_1") (pintype "passive"))
    )
    (net (code "47") (name "Net-(LED1-Pad1)") (class "Default")
      (node (ref "LED1") (pin "1") (pinfunction "1_1") (pintype "passive"))
      (node (ref "R1") (pin "1") (pinfunction "1_1") (pintype "passive"))
    )
    (net (code "48") (name "Net-(Q1-B)") (class "Default")
      (node (ref "Q1") (pin "3") (pinfunction "B_3") (pintype "passive"))
      (node (ref "R24") (pin "1") (pinfunction "1_1") (pintype "passive"))
    )
    (net (code "49") (name "Net-(Q2-B)") (class "Default")
      (node (ref "Q2") (pin "3") (pinfunction "B_3") (pintype "passive"))
      (node (ref "R25") (pin "1") (pinfunction "1_1") (pintype "passive"))
    )
    (net (code "50") (name "Net-(Q3-B)") (class "Default")
      (node (ref "Q3") (pin "3") (pinfunction "B_3") (pintype "passive"))
      (node (ref "R26") (pin "1") (pinfunction "1_1") (pintype "passive"))
    )
    (net (code "51") (name "Net-(Q4-B)") (class "Default")
      (node (ref "Q4") (pin "3") (pinfunction "B_3") (pintype "passive"))
      (node (ref "R27") (pin "1") (pinfunction "1_1") (pintype "passive"))
    )
    (net (code "52") (name "Net-(R11-Pad2)") (class "Default")
      (node (ref "R11") (pin "2") (pinfunction "2_2") (pintype "passive"))
      (node (ref "RED1") (pin "2") (pinfunction "2_2") (pintype "passive"))
    )
    (net (code "53") (name "Net-(R12-Pad2)") (class "Default")
      (node (ref "R12") (pin "2") (pinfunction "2_2") (pintype "passive"))
      (node (ref "YELLOW1") (pin "2") (pinfunction "2_2") (pintype "passive"))
    )
    (net (code "54") (name "Net-(R14-Pad2)") (class "Default")
      (node (ref "R14") (pin "2") (pinfunction "2_2") (pintype "passive"))
      (node (ref "RED2") (pin "2") (pinfunction "2_2") (pintype "passive"))
    )
    (net (code "55") (name "Net-(R15-Pad2)") (class "Default")
      (node (ref "R15") (pin "2") (pinfunction "2_2") (pintype "passive"))
      (node (ref "YELLOW2") (pin "2") (pinfunction "2_2") (pintype "passive"))
    )
    (net (code "56") (name "Net-(R17-Pad2)") (class "Default")
      (node (ref "R17") (pin "2") (pinfunction "2_2") (pintype "passive"))
      (node (ref "RED3") (pin "2") (pinfunction "2_2") (pintype "passive"))
    )
    (net (code "57") (name "Net-(R18-Pad2)") (class "Default")
      (node (ref "R18") (pin "2") (pinfunction "2_2") (pintype "passive"))
      (node (ref "YELLOW3") (pin "2") (pinfunction "2_2") (pintype "passive"))
    )
    (net (code "58") (name "Net-(R20-Pad2)") (class "Default")
      (node (ref "R20") (pin "2") (pinfunction "2_2") (pintype "passive"))
      (node (ref "RED4") (pin "2") (pinfunction "2_2") (pintype "passive"))
    )
    (net (code "59") (name "Net-(R21-Pad2)") (class "Default")
      (node (ref "R21") (pin "2") (pinfunction "2_2") (pintype "passive"))
      (node (ref "YELLOW4") (pin "2") (pinfunction "2_2") (pintype "passive"))
    )
    (net (code "60") (name "Net-(T1-Pri+)") (class "Default")
      (node (ref "JP1") (pin "2") (pinfunction "2_2") (pintype "passive"))
      (node (ref "T1") (pin "1") (pinfunction "Pri+_1") (pintype "passive"))
    )
    (net (code "61") (name "Net-(T1-Pri-)") (class "Default")
      (node (ref "JP1") (pin "1") (pinfunction "1_1") (pintype "passive"))
      (node (ref "T1") (pin "2") (pinfunction "Pri-_2") (pintype "passive"))
    )
    (net (code "62") (name "Net-(T1-Sec+)") (class "Default")
      (node (ref "D1") (pin "4") (pinfunction "C_4") (pintype "passive"))
      (node (ref "T1") (pin "3") (pinfunction "Sec+_3") (pintype "passive"))
    )
    (net (code "63") (name "Net-(T1-Sec-)") (class "Default")
      (node (ref "D1") (pin "2") (pinfunction "C_2") (pintype "passive"))
      (node (ref "T1") (pin "4") (pinfunction "Sec-_4") (pintype "passive"))
    )
    (net (code "64") (name "VCC") (class "Default")
      (node (ref "C2") (pin "2") (pinfunction "2_2") (pintype "passive"))
      (node (ref "C3") (pin "1") (pinfunction "1_1") (pintype "passive"))
      (node (ref "C5") (pin "1") (pinfunction "1_1") (pintype "passive"))
      (node (ref "C6") (pin "2") (pinfunction "2_2") (pintype "passive"))
      (node (ref "IC1") (pin "3") (pinfunction "OUT_3") (pintype "passive"))
      (node (ref "IC2") (pin "31") (pinfunction "~{EA}/VPP_31") (pintype "passive"))
      (node (ref "IC2") (pin "40") (pinfunction "VCC_40") (pintype "power_in"))
      (node (ref "Q1") (pin "1") (pinfunction "E_1") (pintype "passive"))
      (node (ref "Q2") (pin "1") (pinfunction "E_1") (pintype "passive"))
      (node (ref "Q3") (pin "1") (pinfunction "E_1") (pintype "passive"))
      (node (ref "Q4") (pin "1") (pinfunction "E_1") (pintype "passive"))
      (node (ref "R1") (pin "2") (pinfunction "2_2") (pintype "passive"))
      (node (ref "R2") (pin "1") (pinfunction "1_1") (pintype "passive"))
      (node (ref "RPB1") (pin "1") (pinfunction "1_1") (pintype "passive"))
      (node (ref "S1") (pin "2") (pinfunction "2_2") (pintype "passive"))
      (node (ref "YELLOW1") (pin "1") (pinfunction "1_1") (pintype "passive"))
      (node (ref "YELLOW2") (pin "1") (pinfunction "1_1") (pintype "passive"))
      (node (ref "YELLOW3") (pin "1") (pinfunction "1_1") (pintype "passive"))
      (node (ref "YELLOW4") (pin "1") (pinfunction "1_1") (pintype "passive"))
    )
    (net (code "65") (name "unconnected-(IC2-ALE{slash}~{PROG}-Pad30)") (class "Default")
      (node (ref "IC2") (pin "30") (pinfunction "ALE/~{PROG}_30") (pintype "passive"))
    )
    (net (code "66") (name "unconnected-(IC2-P1.2-Pad3)") (class "Default")
      (node (ref "IC2") (pin "3") (pinfunction "P1.2_3") (pintype "passive"))
    )
    (net (code "67") (name "unconnected-(IC2-P1.3-Pad4)") (class "Default")
      (node (ref "IC2") (pin "4") (pinfunction "P1.3_4") (pintype "passive"))
    )
    (net (code "68") (name "unconnected-(IC2-P1.4-Pad5)") (class "Default")
      (node (ref "IC2") (pin "5") (pinfunction "P1.4_5") (pintype "passive"))
    )
    (net (code "69") (name "unconnected-(IC2-P1.5{slash}MOSI-Pad6)") (class "Default")
      (node (ref "IC2") (pin "6") (pinfunction "P1.5/MOSI_6") (pintype "passive"))
    )
    (net (code "70") (name "unconnected-(IC2-P1.6{slash}MISO-Pad7)") (class "Default")
      (node (ref "IC2") (pin "7") (pinfunction "P1.6/MISO_7") (pintype "passive"))
    )
    (net (code "71") (name "unconnected-(IC2-P1.7{slash}SCK-Pad8)") (class "Default")
      (node (ref "IC2") (pin "8") (pinfunction "P1.7/SCK_8") (pintype "passive"))
    )
    (net (code "72") (name "unconnected-(IC2-P2.6{slash}A14-Pad27)") (class "Default")
      (node (ref "IC2") (pin "27") (pinfunction "P2.6/A14_27") (pintype "passive"))
    )
    (net (code "73") (name "unconnected-(IC2-P2.7{slash}A15-Pad28)") (class "Default")
      (node (ref "IC2") (pin "28") (pinfunction "P2.7/A15_28") (pintype "passive"))
    )
    (net (code "74") (name "unconnected-(IC2-RXD{slash}P3.0-Pad10)") (class "Default")
      (node (ref "IC2") (pin "10") (pinfunction "RXD/P3.0_10") (pintype "passive"))
    )
    (net (code "75") (name "unconnected-(IC2-T2_EX{slash}P1.1-Pad2)") (class "Default")
      (node (ref "IC2") (pin "2") (pinfunction "T2_EX/P1.1_2") (pintype "passive"))
    )
    (net (code "76") (name "unconnected-(IC2-T2{slash}P1.0-Pad1)") (class "Default")
      (node (ref "IC2") (pin "1") (pinfunction "T2/P1.0_1") (pintype "passive"))
    )
    (net (code "77") (name "unconnected-(IC2-TXD{slash}P3.1-Pad11)") (class "Default")
      (node (ref "IC2") (pin "11") (pinfunction "TXD/P3.1_11") (pintype "passive"))
    )
    (net (code "78") (name "unconnected-(IC2-~{INT1}{slash}P3.3-Pad13)") (class "Default")
      (node (ref "IC2") (pin "13") (pinfunction "~{INT1}/P3.3_13") (pintype "passive"))
    )
    (net (code "79") (name "unconnected-(IC2-~{PSEN}-Pad29)") (class "Default")
      (node (ref "IC2") (pin "29") (pinfunction "~{PSEN}_29") (pintype "passive"))
    )
  )
)
